# SCH_MinijetengineECU_20260709.net
KiCad netlist of a schematic drawn in EasyEDA
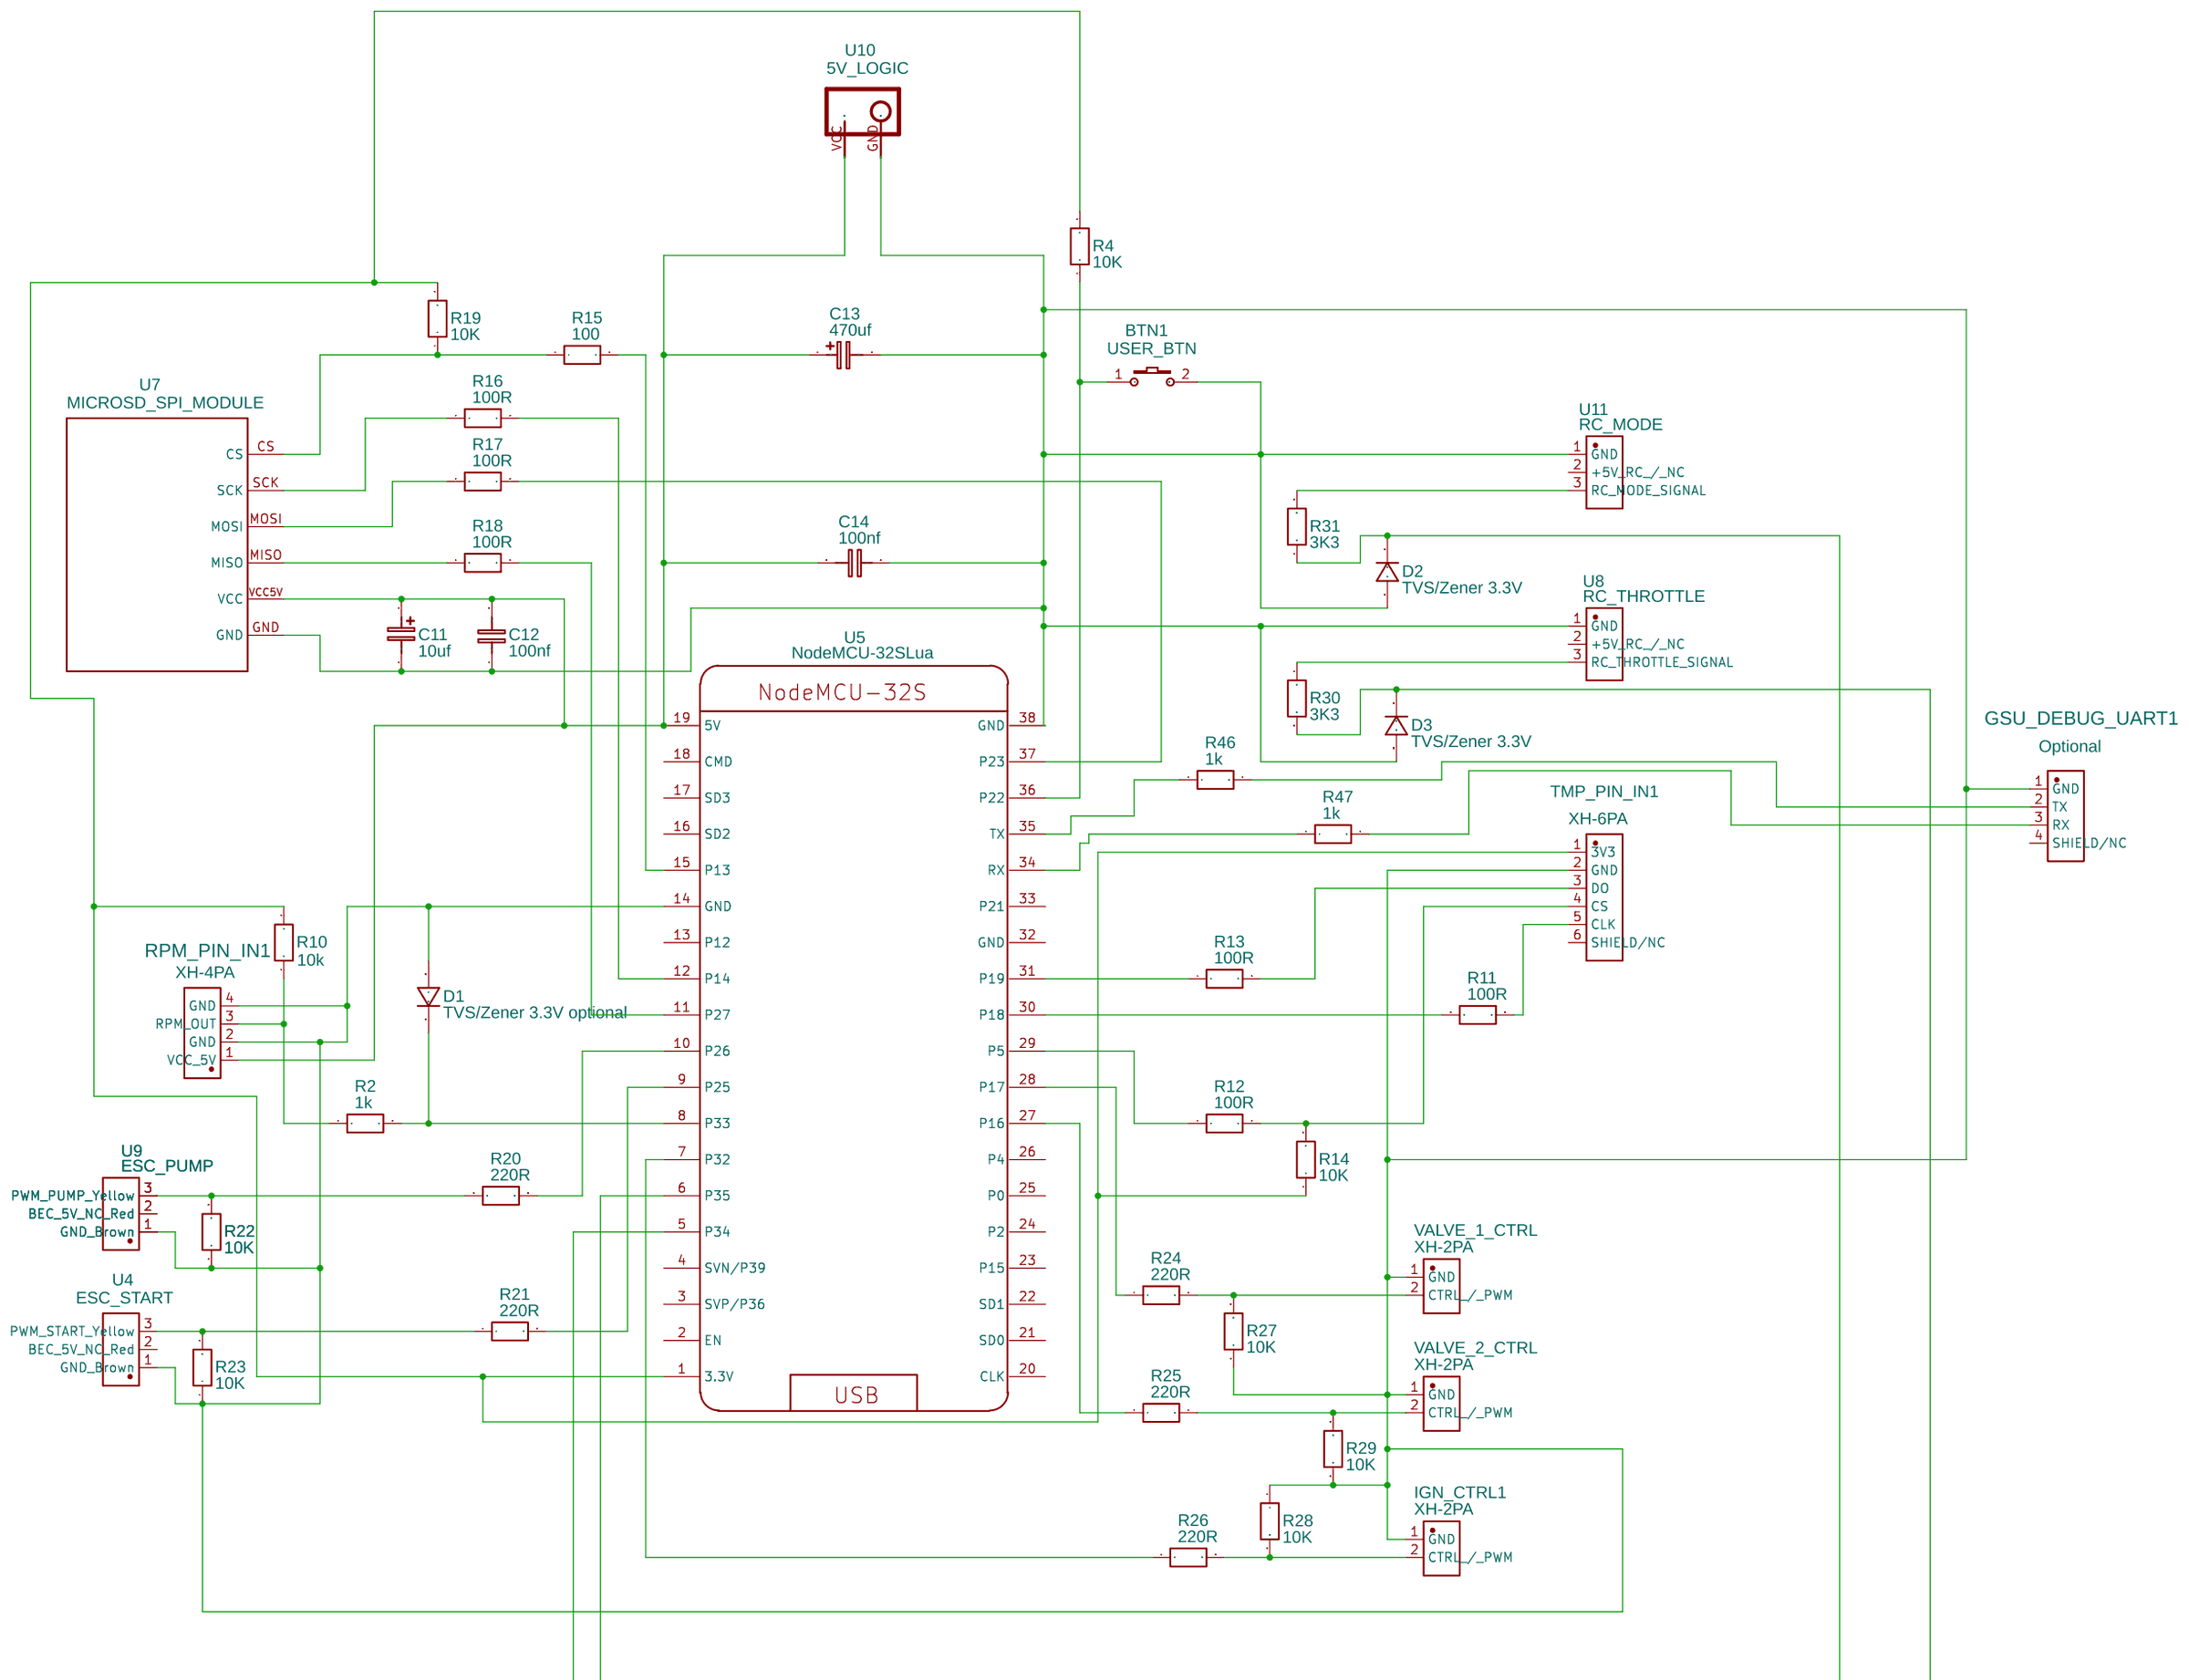
[diagram p0: ECU_JET]
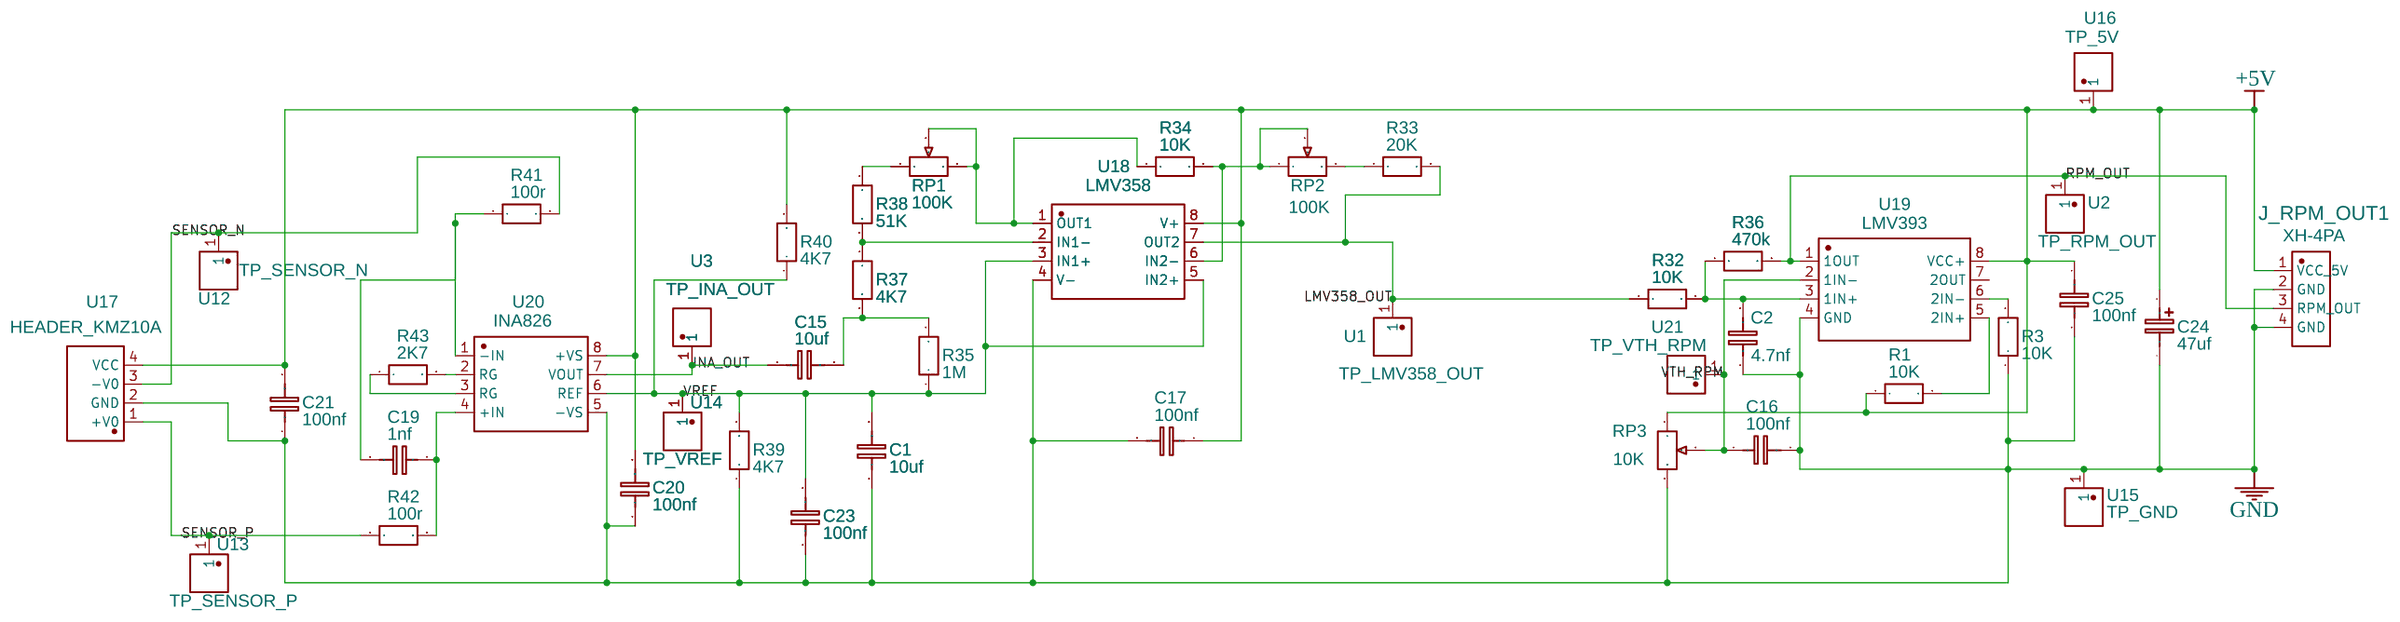
[diagram p1: RPM_Sensor]
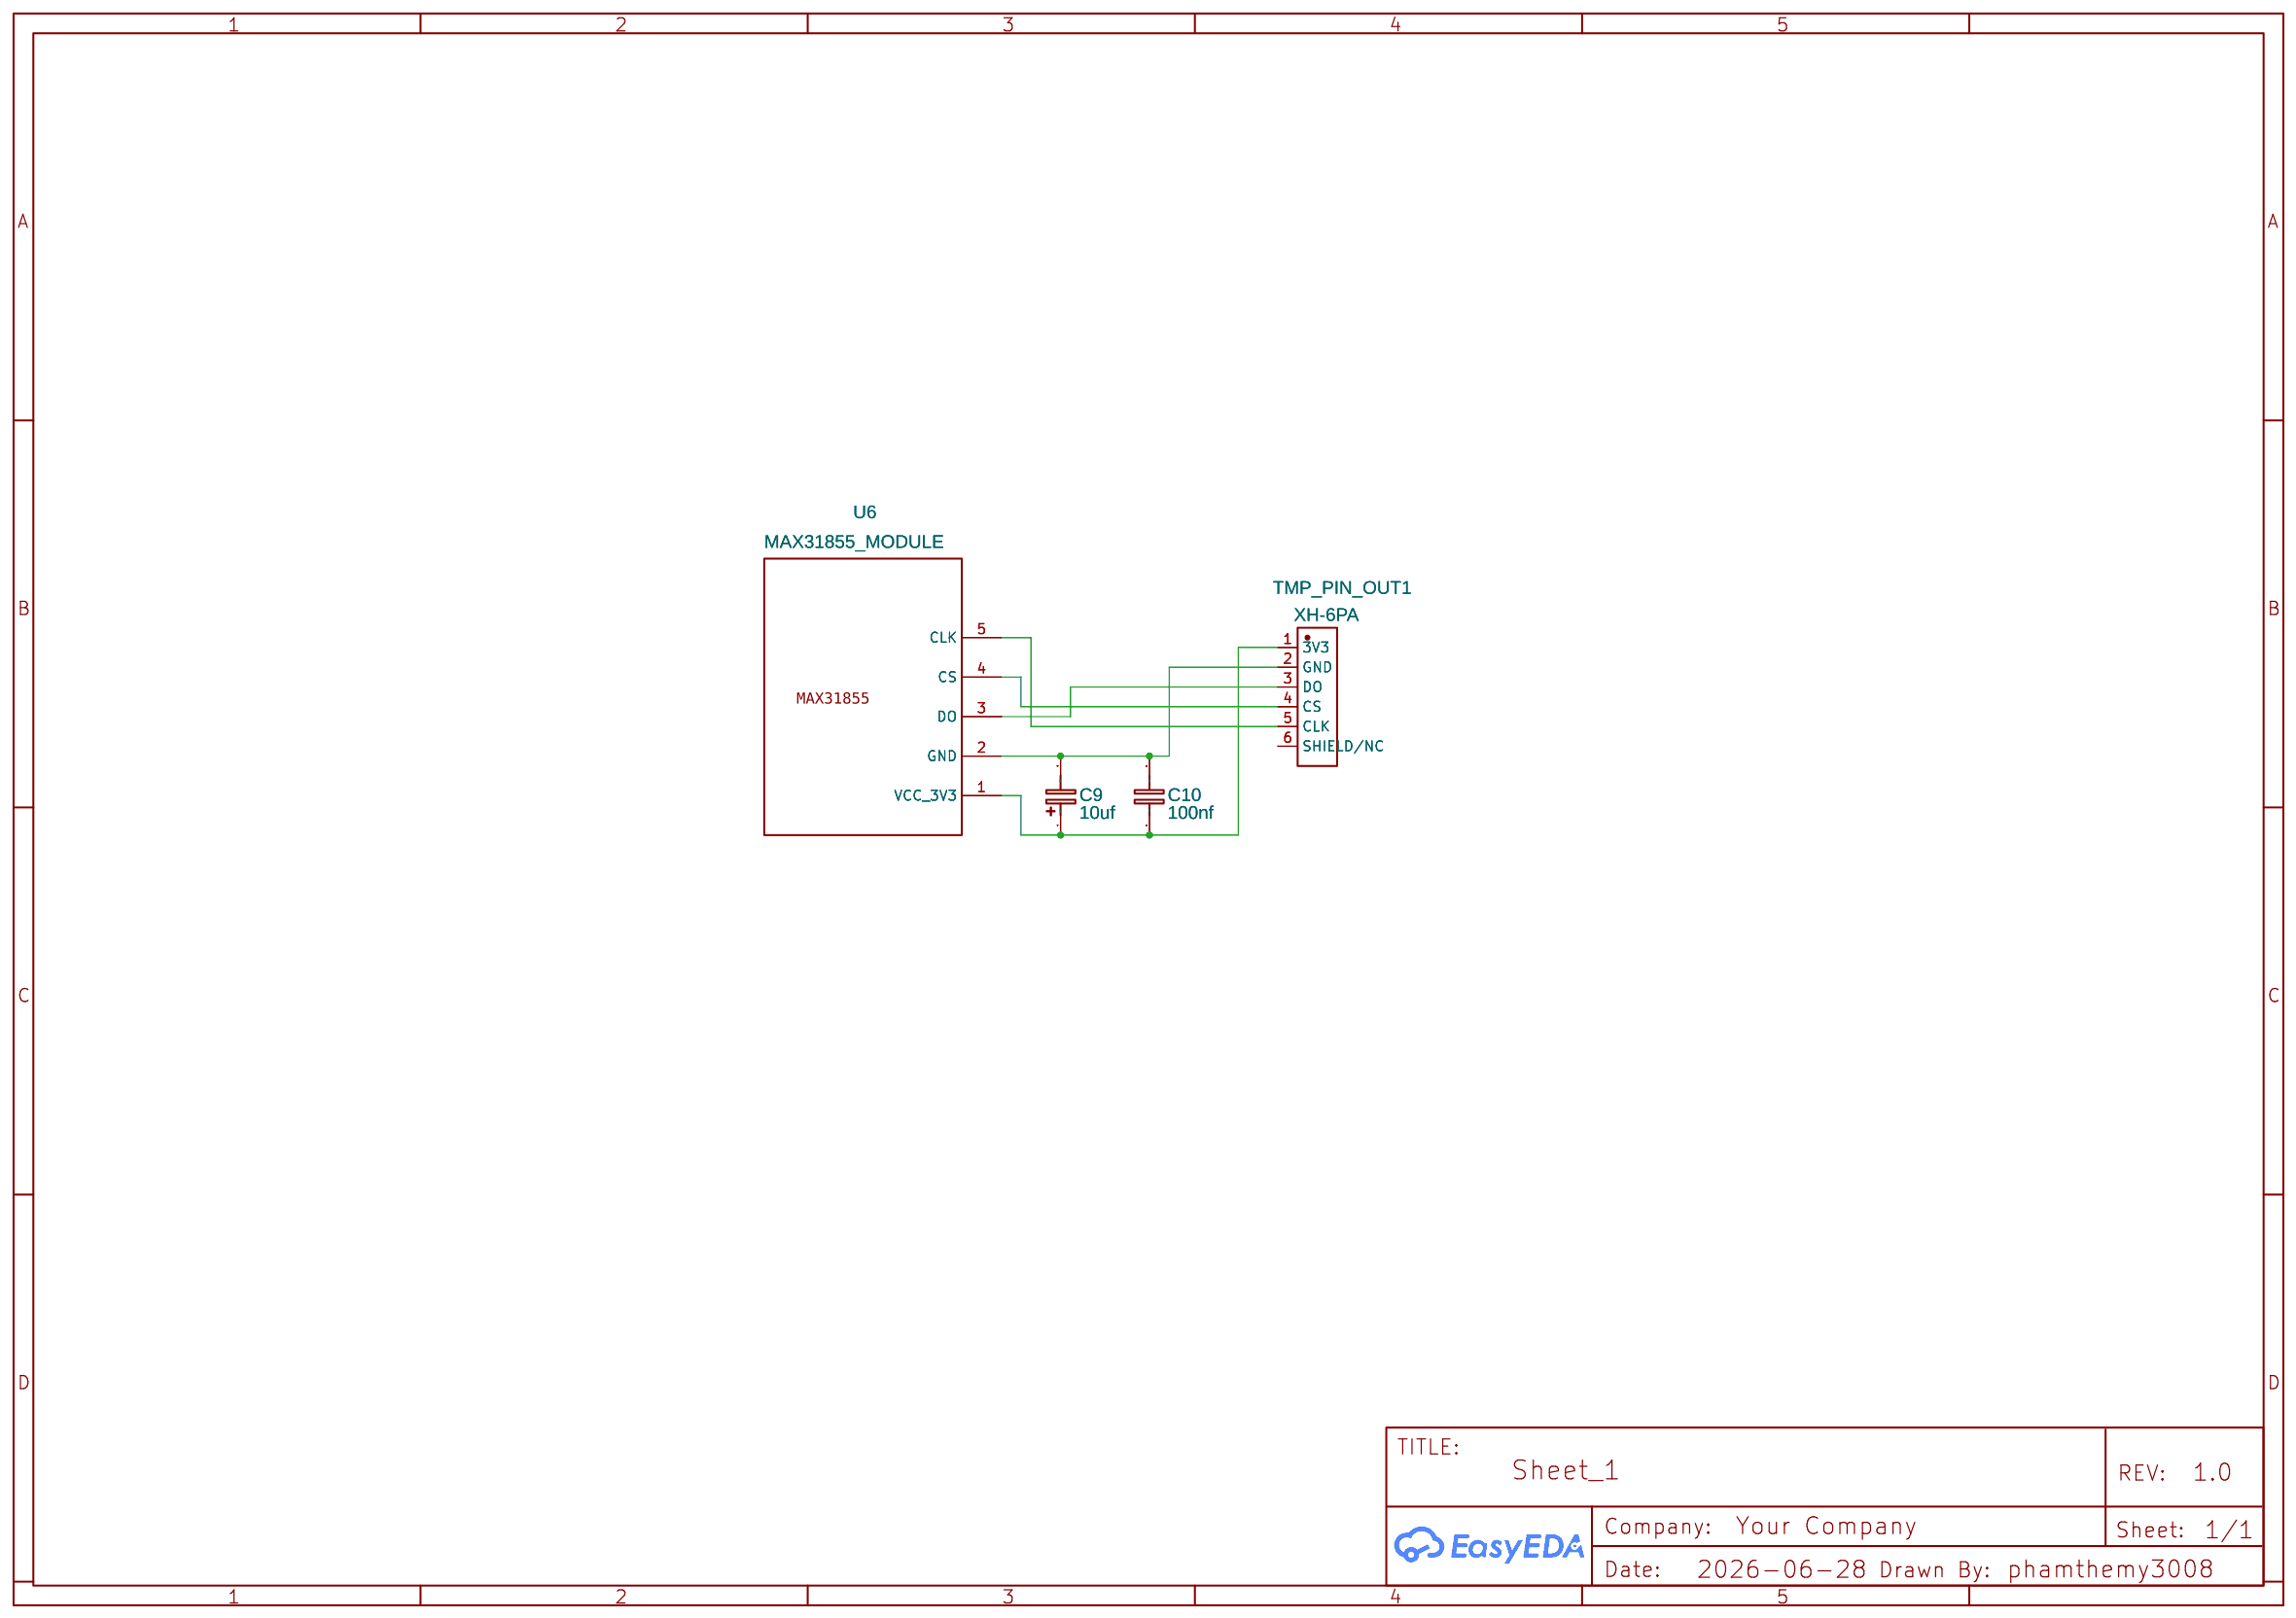
[diagram p2: Temperature_Sensor]

(export (version "E")
  (design (tool "Eeschema 10.0.6"))
  (components
    (comp (ref "BTN1")
      (value "USER_BTN")
      (fields (field (name "Manufacturer Part") "K2-1107ST-A4SW-06"))
      (libsource (lib "") (part "K2-3.6×6.1_SMD"))
    )
    (comp (ref "C11") (value "10uf") (libsource (lib "") (part "C_Tan_SMD_A_EU")))
    (comp (ref "C12") (value "100nf") (libsource (lib "") (part "C_0603_EU_1")))
    (comp (ref "C13") (value "470uf") (libsource (lib "") (part "C_Tan_SMD_A_EU_1")))
    (comp (ref "C14") (value "100nf") (libsource (lib "") (part "C_0603_EU")))
    (comp (ref "D1") (value "TVS/Zener 3.3V optional") (libsource (lib "") (part "1N4007W_1")))
    (comp (ref "D2") (value "TVS/Zener 3.3V") (libsource (lib "") (part "1N4007W")))
    (comp (ref "D3") (value "TVS/Zener 3.3V") (libsource (lib "") (part "1N4007W")))
    (comp (ref "GSU_DEBUG_UART1")
      (value "Optional")
      (fields (field (name "Manufacturer Part") "XH-4PA") (field (name "Manufacturer") "ZHOURI(洲日)"))
      (libsource (lib "") (part "XH-4PA_1"))
    )
    (comp (ref "IGN_CTRL1")
      (value "XH-2PA")
      (fields (field (name "Manufacturer") "ZHOURI(洲日)"))
      (libsource (lib "") (part "XH-2PA_2"))
    )
    (comp (ref "R2") (value "1k") (libsource (lib "") (part "R_0603_EU")))
    (comp (ref "R4") (value "10K") (libsource (lib "") (part "R_0603_EU_1")))
    (comp (ref "R10") (value "10k") (libsource (lib "") (part "R_0603_EU_1")))
    (comp (ref "R11") (value "100R") (libsource (lib "") (part "R_0603_EU")))
    (comp (ref "R12") (value "100R") (libsource (lib "") (part "R_0603_EU")))
    (comp (ref "R13") (value "100R") (libsource (lib "") (part "R_0603_EU")))
    (comp (ref "R14") (value "10K") (libsource (lib "") (part "R_0603_EU_1")))
    (comp (ref "R15") (value "100") (libsource (lib "") (part "R_0603_EU")))
    (comp (ref "R16") (value "100R") (libsource (lib "") (part "R_0603_EU")))
    (comp (ref "R17") (value "100R") (libsource (lib "") (part "R_0603_EU")))
    (comp (ref "R18") (value "100R") (libsource (lib "") (part "R_0603_EU")))
    (comp (ref "R19") (value "10K") (libsource (lib "") (part "R_0603_EU_1")))
    (comp (ref "R20") (value "220R") (libsource (lib "") (part "R_0603_EU")))
    (comp (ref "R21") (value "220R") (libsource (lib "") (part "R_0603_EU")))
    (comp (ref "R22") (value "10K") (libsource (lib "") (part "R_0603_EU_1")))
    (comp (ref "R23") (value "10K") (libsource (lib "") (part "R_0603_EU_1")))
    (comp (ref "R24") (value "220R") (libsource (lib "") (part "R_0603_EU")))
    (comp (ref "R25") (value "220R") (libsource (lib "") (part "R_0603_EU")))
    (comp (ref "R26") (value "220R") (libsource (lib "") (part "R_0603_EU")))
    (comp (ref "R27") (value "10K") (libsource (lib "") (part "R_0603_EU_1")))
    (comp (ref "R28") (value "10K") (libsource (lib "") (part "R_0603_EU_2")))
    (comp (ref "R29") (value "10K") (libsource (lib "") (part "R_0603_EU_1")))
    (comp (ref "R30") (value "3K3") (libsource (lib "") (part "R_0603_EU_2")))
    (comp (ref "R31") (value "3K3") (libsource (lib "") (part "R_0603_EU_1")))
    (comp (ref "R46") (value "1k") (libsource (lib "") (part "R_0603_EU")))
    (comp (ref "R47") (value "1k") (libsource (lib "") (part "R_0603_EU")))
    (comp (ref "RPM_PIN_IN1")
      (value "XH-4PA")
      (fields (field (name "Manufacturer") "ZHOURI(洲日)"))
      (libsource (lib "") (part "XH-4PA"))
    )
    (comp (ref "TMP_PIN_IN1")
      (value "XH-6PA")
      (fields (field (name "Manufacturer") "ZHOURI(洲日)"))
      (libsource (lib "") (part "XH-6PA"))
    )
    (comp (ref "U4")
      (value "ESC_START")
      (fields (field (name "Manufacturer Part") "Header35.08-3P"))
      (libsource (lib "") (part "HEADER35.08-3P"))
    )
    (comp (ref "U5")
      (value "NodeMCU-32SLua")
      (fields (field (name "Manufacturer") "Ai-Thinker"))
      (libsource (lib "") (part "NodeMCU-32SLua"))
    )
    (comp (ref "U7") (value "MICROSD_SPI_MODULE") (libsource (lib "") (part "MICROSD_SPI_MODULE")))
    (comp (ref "U8")
      (value "RC_THROTTLE")
      (fields (field (name "Manufacturer Part") "Header35.08-3P"))
      (libsource (lib "") (part "HEADER35.08-3P_1"))
    )
    (comp (ref "U9")
      (value "ESC_PUMP")
      (fields (field (name "Manufacturer Part") "Header35.08-3P"))
      (libsource (lib "") (part "HEADER35.08-3P_3"))
    )
    (comp (ref "U10") (value "5V_LOGIC") (libsource (lib "") (part "DOMINO-2P-5.08")))
    (comp (ref "U11")
      (value "RC_MODE")
      (fields (field (name "Manufacturer Part") "Header35.08-3P"))
      (libsource (lib "") (part "HEADER35.08-3P_2"))
    )
    (comp (ref "VALVE_1_CTRL")
      (value "XH-2PA")
      (fields (field (name "Manufacturer") "ZHOURI(洲日)"))
      (libsource (lib "") (part "XH-2PA"))
    )
    (comp (ref "VALVE_2_CTRL")
      (value "XH-2PA")
      (fields (field (name "Manufacturer") "ZHOURI(洲日)"))
      (libsource (lib "") (part "XH-2PA_1"))
    )
    (comp (ref "C1") (value "10uf") (libsource (lib "") (part "C_0603_EU")))
    (comp (ref "C2") (value "4.7nf") (libsource (lib "") (part "C_0603_EU_1")))
    (comp (ref "C15") (value "10uf") (libsource (lib "") (part "C_0603_EU_4")))
    (comp (ref "C16") (value "100nf") (libsource (lib "") (part "C_0603_EU_3")))
    (comp (ref "C17") (value "100nf") (libsource (lib "") (part "C_0603_EU_5")))
    (comp (ref "C19") (value "1nf") (libsource (lib "") (part "C_0603_EU_2")))
    (comp (ref "C20") (value "100nf") (libsource (lib "") (part "C_0603_EU")))
    (comp (ref "C21") (value "100nf") (libsource (lib "") (part "C_0603_EU")))
    (comp (ref "C23") (value "100nf") (libsource (lib "") (part "C_0603_EU")))
    (comp (ref "C24")
      (value "47uf")
      (fields (field (name "Manufacturer Part") "TAJB476K010RNJ") (field (name "Manufacturer") "Kyocera AVX"))
      (libsource (lib "") (part "C_Tan_SMD_A_EU"))
    )
    (comp (ref "C25") (value "100nf") (libsource (lib "") (part "C_0603_EU_6")))
    (comp (ref "J_RPM_OUT1")
      (value "XH-4PA")
      (fields (field (name "Manufacturer") "ZHOURI(洲日)"))
      (libsource (lib "") (part "XH-4PA"))
    )
    (comp (ref "R1") (value "10K") (libsource (lib "") (part "R_0603_EU")))
    (comp (ref "R3") (value "10K") (libsource (lib "") (part "R_0603_EU_2")))
    (comp (ref "R32") (value "10K") (libsource (lib "") (part "R_0603_EU")))
    (comp (ref "R33") (value "20K") (libsource (lib "") (part "R_0603_EU")))
    (comp (ref "R34") (value "10K") (libsource (lib "") (part "R_0603_EU")))
    (comp (ref "R35") (value "1M") (libsource (lib "") (part "R_0603_EU_2")))
    (comp (ref "R36") (value "470k") (libsource (lib "") (part "R_0603_EU")))
    (comp (ref "R37") (value "4K7") (libsource (lib "") (part "R_0603_EU_1")))
    (comp (ref "R38") (value "51K") (libsource (lib "") (part "R_0603_EU_1")))
    (comp (ref "R39") (value "4K7") (libsource (lib "") (part "R_0603_EU_2")))
    (comp (ref "R40") (value "4K7") (libsource (lib "") (part "R_0603_EU_2")))
    (comp (ref "R41") (value "100r") (libsource (lib "") (part "R_0603_EU")))
    (comp (ref "R42") (value "100r") (libsource (lib "") (part "R_0603_EU")))
    (comp (ref "R43") (value "2K7") (libsource (lib "") (part "R_0603_EU")))
    (comp (ref "RP1") (value "100K") (libsource (lib "") (part "R_3386P_EU")))
    (comp (ref "RP2") (value "100K") (libsource (lib "") (part "R_3386P_EU")))
    (comp (ref "RP3") (value "10K") (libsource (lib "") (part "R_3386P_EU_1")))
    (comp (ref "U1")
      (value "TP_LMV358_OUT")
      (fields
        (field (name "Manufacturer Part") "YZP0352-20095-01")
        (field (name "Manufacturer") "Xinyangze(鑫扬泽)")
      )
      (libsource (lib "") (part "YZP0352-20095-01_1"))
    )
    (comp (ref "U2")
      (value "TP_RPM_OUT")
      (fields
        (field (name "Manufacturer Part") "YZP0352-20095-01")
        (field (name "Manufacturer") "Xinyangze(鑫扬泽)")
      )
      (libsource (lib "") (part "YZP0352-20095-01_1"))
    )
    (comp (ref "U3")
      (value "TP_INA_OUT")
      (fields
        (field (name "Manufacturer Part") "YZP0352-20095-01")
        (field (name "Manufacturer") "Xinyangze(鑫扬泽)")
      )
      (libsource (lib "") (part "YZP0352-20095-01"))
    )
    (comp (ref "U12")
      (value "TP_SENSOR_N")
      (fields
        (field (name "Manufacturer Part") "YZP0352-20095-01")
        (field (name "Manufacturer") "Xinyangze(鑫扬泽)")
      )
      (libsource (lib "") (part "YZP0352-20095-01_1"))
    )
    (comp (ref "U13")
      (value "TP_SENSOR_P")
      (fields
        (field (name "Manufacturer Part") "YZP0352-20095-01")
        (field (name "Manufacturer") "Xinyangze(鑫扬泽)")
      )
      (libsource (lib "") (part "YZP0352-20095-01_1"))
    )
    (comp (ref "U14")
      (value "TP_VREF")
      (fields
        (field (name "Manufacturer Part") "YZP0352-20095-01")
        (field (name "Manufacturer") "Xinyangze(鑫扬泽)")
      )
      (libsource (lib "") (part "YZP0352-20095-01_1"))
    )
    (comp (ref "U15")
      (value "TP_GND")
      (fields
        (field (name "Manufacturer Part") "YZP0352-20095-01")
        (field (name "Manufacturer") "Xinyangze(鑫扬泽)")
      )
      (libsource (lib "") (part "YZP0352-20095-01_1"))
    )
    (comp (ref "U16")
      (value "TP_5V")
      (fields
        (field (name "Manufacturer Part") "YZP0352-20095-01")
        (field (name "Manufacturer") "Xinyangze(鑫扬泽)")
      )
      (libsource (lib "") (part "YZP0352-20095-01"))
    )
    (comp (ref "U17") (value "HEADER_KMZ10A") (libsource (lib "") (part "Magnetic Sensor")))
    (comp (ref "U18")
      (value "LMV358")
      (fields (field (name "Manufacturer") "TECH PUBLIC"))
      (libsource (lib "") (part "LM358DGKRG"))
    )
    (comp (ref "U19")
      (value "LMV393")
      (fields (field (name "Manufacturer Part") "LMV393IDR") (field (name "Manufacturer") "TI(德州仪器)"))
      (libsource (lib "") (part "LMV393IDR"))
    )
    (comp (ref "U20")
      (value "INA826")
      (fields (field (name "Manufacturer Part") "INA826AID") (field (name "Manufacturer") "TI(德州仪器)"))
      (libsource (lib "") (part "INA826AID"))
    )
    (comp (ref "U21")
      (value "TP_VTH_RPM")
      (fields
        (field (name "Manufacturer Part") "YZP0352-20095-01")
        (field (name "Manufacturer") "Xinyangze(鑫扬泽)")
      )
      (libsource (lib "") (part "YZP0352-20095-01_2"))
    )
    (comp (ref "C9") (value "10uf") (libsource (lib "") (part "C_Tan_SMD_A_EU")))
    (comp (ref "C10") (value "100nf") (libsource (lib "") (part "C_0603_EU")))
    (comp (ref "TMP_PIN_OUT1")
      (value "XH-6PA")
      (fields (field (name "Manufacturer") "ZHOURI(洲日)"))
      (libsource (lib "") (part "XH-6PA"))
    )
    (comp (ref "U6") (value "MAX31855_MODULE") (libsource (lib "") (part "MAX31855_MODULE")))
  )
  (nets
    (net (code "1") (name "+5V") (class "Default")
      (node (ref "C17") (pin "1") (pinfunction "1_1") (pintype "unspecified"))
      (node (ref "C20") (pin "2") (pinfunction "2_2") (pintype "unspecified"))
      (node (ref "C21") (pin "2") (pinfunction "2_2") (pintype "unspecified"))
      (node (ref "C24") (pin "+") (pinfunction "1_+") (pintype "unspecified"))
      (node (ref "C25") (pin "1") (pinfunction "2_1") (pintype "unspecified"))
      (node (ref "J_RPM_OUT1") (pin "1") (pinfunction "VCC_5V_1") (pintype "unspecified"))
      (node (ref "R1") (pin "1") (pinfunction "1_1") (pintype "unspecified"))
      (node (ref "R40") (pin "2") (pinfunction "2_2") (pintype "unspecified"))
      (node (ref "RP3") (pin "1") (pinfunction "1_1") (pintype "input"))
      (node (ref "U16") (pin "1") (pinfunction "1_1") (pintype "unspecified"))
      (node (ref "U17") (pin "4") (pinfunction "VCC_4") (pintype "unspecified"))
      (node (ref "U18") (pin "8") (pinfunction "V+_8") (pintype "unspecified"))
      (node (ref "U19") (pin "8") (pinfunction "VCC+_8") (pintype "unspecified"))
      (node (ref "U20") (pin "8") (pinfunction "+VS_8") (pintype "unspecified"))
    )
    (net (code "2") (name "GND") (class "Default")
      (node (ref "C1") (pin "1") (pinfunction "1_1") (pintype "unspecified"))
      (node (ref "C16") (pin "2") (pinfunction "2_2") (pintype "unspecified"))
      (node (ref "C17") (pin "2") (pinfunction "2_2") (pintype "unspecified"))
      (node (ref "C2") (pin "1") (pinfunction "1_1") (pintype "unspecified"))
      (node (ref "C20") (pin "1") (pinfunction "1_1") (pintype "unspecified"))
      (node (ref "C21") (pin "1") (pinfunction "1_1") (pintype "unspecified"))
      (node (ref "C23") (pin "1") (pinfunction "1_1") (pintype "unspecified"))
      (node (ref "C24") (pin "-") (pinfunction "2_-") (pintype "unspecified"))
      (node (ref "C25") (pin "2") (pinfunction "1_2") (pintype "unspecified"))
      (node (ref "J_RPM_OUT1") (pin "2") (pinfunction "GND_2") (pintype "unspecified"))
      (node (ref "J_RPM_OUT1") (pin "4") (pinfunction "GND_4") (pintype "unspecified"))
      (node (ref "R3") (pin "1") (pinfunction "1_1") (pintype "unspecified"))
      (node (ref "R39") (pin "1") (pinfunction "1_1") (pintype "unspecified"))
      (node (ref "RP3") (pin "3") (pinfunction "3_3") (pintype "input"))
      (node (ref "U15") (pin "1") (pinfunction "1_1") (pintype "unspecified"))
      (node (ref "U17") (pin "2") (pinfunction "GND_2") (pintype "unspecified"))
      (node (ref "U18") (pin "4") (pinfunction "V-_4") (pintype "unspecified"))
      (node (ref "U19") (pin "4") (pinfunction "GND_4") (pintype "unspecified"))
      (node (ref "U20") (pin "5") (pinfunction "-VS_5") (pintype "unspecified"))
    )
    (net (code "3") (name "INA_OUT") (class "Default")
      (node (ref "C15") (pin "1") (pinfunction "1_1") (pintype "unspecified"))
      (node (ref "U20") (pin "7") (pinfunction "VOUT_7") (pintype "unspecified"))
      (node (ref "U3") (pin "1") (pinfunction "1_1") (pintype "unspecified"))
    )
    (net (code "4") (name "LMV358_OUT") (class "Default")
      (node (ref "R32") (pin "1") (pinfunction "1_1") (pintype "unspecified"))
      (node (ref "R33") (pin "2") (pinfunction "2_2") (pintype "unspecified"))
      (node (ref "U1") (pin "1") (pinfunction "1_1") (pintype "unspecified"))
      (node (ref "U18") (pin "7") (pinfunction "OUT2_7") (pintype "unspecified"))
    )
    (net (code "5") (name "Net-(C15-Pad2)") (class "Default")
      (node (ref "C15") (pin "2") (pinfunction "2_2") (pintype "unspecified"))
      (node (ref "R35") (pin "2") (pinfunction "2_2") (pintype "unspecified"))
      (node (ref "R37") (pin "2") (pinfunction "2_2") (pintype "unspecified"))
    )
    (net (code "6") (name "Net-(D1-1)") (class "Default")
      (node (ref "D1") (pin "P$1") (pinfunction "1_P$1") (pintype "unspecified"))
      (node (ref "R2") (pin "2") (pinfunction "2_2") (pintype "unspecified"))
      (node (ref "U5") (pin "8") (pinfunction "P33_8") (pintype "unspecified"))
    )
    (net (code "7") (name "Net-(D1-2)") (class "Default")
      (node (ref "BTN1") (pin "2") (pinfunction "2_2") (pintype "unspecified"))
      (node (ref "C11") (pin "2") (pinfunction "2_2") (pintype "unspecified"))
      (node (ref "C12") (pin "1") (pinfunction "1_1") (pintype "unspecified"))
      (node (ref "C13") (pin "2") (pinfunction "2_2") (pintype "unspecified"))
      (node (ref "C14") (pin "1") (pinfunction "1_1") (pintype "unspecified"))
      (node (ref "D1") (pin "P$2") (pinfunction "2_P$2") (pintype "unspecified"))
      (node (ref "D2") (pin "P$2") (pinfunction "2_P$2") (pintype "unspecified"))
      (node (ref "D3") (pin "P$2") (pinfunction "2_P$2") (pintype "unspecified"))
      (node (ref "GSU_DEBUG_UART1") (pin "1") (pinfunction "GND_1") (pintype "unspecified"))
      (node (ref "IGN_CTRL1") (pin "1") (pinfunction "GND_1") (pintype "unspecified"))
      (node (ref "R22") (pin "1") (pinfunction "1_1") (pintype "unspecified"))
      (node (ref "R23") (pin "1") (pinfunction "1_1") (pintype "unspecified"))
      (node (ref "R27") (pin "1") (pinfunction "1_1") (pintype "unspecified"))
      (node (ref "R28") (pin "1") (pinfunction "1_1") (pintype "unspecified"))
      (node (ref "R29") (pin "1") (pinfunction "1_1") (pintype "unspecified"))
      (node (ref "RPM_PIN_IN1") (pin "2") (pinfunction "GND_2") (pintype "unspecified"))
      (node (ref "RPM_PIN_IN1") (pin "4") (pinfunction "GND_4") (pintype "unspecified"))
      (node (ref "TMP_PIN_IN1") (pin "2") (pinfunction "GND_2") (pintype "unspecified"))
      (node (ref "U10") (pin "GND") (pinfunction "GND_GND") (pintype "passive"))
      (node (ref "U11") (pin "1") (pinfunction "GND_1") (pintype "unspecified"))
      (node (ref "U4") (pin "1") (pinfunction "GND_Brown_1") (pintype "unspecified"))
      (node (ref "U5") (pin "14") (pinfunction "GND_14") (pintype "unspecified"))
      (node (ref "U5") (pin "38") (pinfunction "GND_38") (pintype "unspecified"))
      (node (ref "U7") (pin "GND") (pinfunction "GND_GND") (pintype "input"))
      (node (ref "U8") (pin "1") (pinfunction "GND_1") (pintype "unspecified"))
      (node (ref "U9") (pin "1") (pinfunction "GND_Brown_1") (pintype "unspecified"))
      (node (ref "VALVE_1_CTRL") (pin "1") (pinfunction "GND_1") (pintype "unspecified"))
      (node (ref "VALVE_2_CTRL") (pin "1") (pinfunction "GND_1") (pintype "unspecified"))
    )
    (net (code "8") (name "Net-(D2-1)") (class "Default")
      (node (ref "D2") (pin "P$1") (pinfunction "1_P$1") (pintype "unspecified"))
      (node (ref "R31") (pin "1") (pinfunction "1_1") (pintype "unspecified"))
      (node (ref "U5") (pin "6") (pinfunction "P35_6") (pintype "unspecified"))
    )
    (net (code "9") (name "Net-(D3-1)") (class "Default")
      (node (ref "D3") (pin "P$1") (pinfunction "1_P$1") (pintype "unspecified"))
      (node (ref "R30") (pin "2") (pinfunction "2_2") (pintype "unspecified"))
      (node (ref "U5") (pin "5") (pinfunction "P34_5") (pintype "unspecified"))
    )
    (net (code "10") (name "Net-(GSU_DEBUG_UART1-RX)") (class "Default")
      (node (ref "GSU_DEBUG_UART1") (pin "3") (pinfunction "RX_3") (pintype "unspecified"))
      (node (ref "R47") (pin "2") (pinfunction "2_2") (pintype "unspecified"))
    )
    (net (code "11") (name "Net-(GSU_DEBUG_UART1-TX)") (class "Default")
      (node (ref "GSU_DEBUG_UART1") (pin "2") (pinfunction "TX_2") (pintype "unspecified"))
      (node (ref "R46") (pin "2") (pinfunction "2_2") (pintype "unspecified"))
    )
    (net (code "12") (name "Net-(IGN_CTRL1-CTRL_{slash}_PWM)") (class "Default")
      (node (ref "IGN_CTRL1") (pin "2") (pinfunction "CTRL_/_PWM_2") (pintype "unspecified"))
      (node (ref "R26") (pin "2") (pinfunction "2_2") (pintype "unspecified"))
      (node (ref "R28") (pin "2") (pinfunction "2_2") (pintype "unspecified"))
    )
    (net (code "13") (name "Net-(R15-Pad1)") (class "Default")
      (node (ref "R15") (pin "1") (pinfunction "1_1") (pintype "unspecified"))
      (node (ref "R19") (pin "1") (pinfunction "1_1") (pintype "unspecified"))
      (node (ref "U7") (pin "CS") (pinfunction "CS_CS") (pintype "bidirectional"))
    )
    (net (code "14") (name "Net-(R16-Pad1)") (class "Default")
      (node (ref "R16") (pin "1") (pinfunction "1_1") (pintype "unspecified"))
      (node (ref "U7") (pin "SCK") (pinfunction "SCK_SCK") (pintype "bidirectional"))
    )
    (net (code "15") (name "Net-(R17-Pad1)") (class "Default")
      (node (ref "R17") (pin "1") (pinfunction "1_1") (pintype "unspecified"))
      (node (ref "U7") (pin "MOSI") (pinfunction "MOSI_MOSI") (pintype "input"))
    )
    (net (code "16") (name "Net-(R18-Pad1)") (class "Default")
      (node (ref "R18") (pin "1") (pinfunction "1_1") (pintype "unspecified"))
      (node (ref "U7") (pin "MISO") (pinfunction "MISO_MISO") (pintype "output"))
    )
    (net (code "17") (name "Net-(R33-Pad1)") (class "Default")
      (node (ref "R33") (pin "1") (pinfunction "1_1") (pintype "unspecified"))
      (node (ref "RP2") (pin "3") (pinfunction "3_3") (pintype "input"))
    )
    (net (code "18") (name "Net-(R38-Pad1)") (class "Default")
      (node (ref "R38") (pin "1") (pinfunction "1_1") (pintype "unspecified"))
      (node (ref "RP1") (pin "1") (pinfunction "1_1") (pintype "input"))
    )
    (net (code "19") (name "Net-(R43-Pad1)") (class "Default")
      (node (ref "R43") (pin "1") (pinfunction "1_1") (pintype "unspecified"))
      (node (ref "U20") (pin "3") (pinfunction "RG_3") (pintype "unspecified"))
    )
    (net (code "20") (name "Net-(R43-Pad2)") (class "Default")
      (node (ref "R43") (pin "2") (pinfunction "2_2") (pintype "unspecified"))
      (node (ref "U20") (pin "2") (pinfunction "RG_2") (pintype "unspecified"))
    )
    (net (code "21") (name "Net-(RPM_PIN_IN1-RPM_OUT)") (class "Default")
      (node (ref "R10") (pin "1") (pinfunction "1_1") (pintype "unspecified"))
      (node (ref "R2") (pin "1") (pinfunction "1_1") (pintype "unspecified"))
      (node (ref "RPM_PIN_IN1") (pin "3") (pinfunction "RPM_OUT_3") (pintype "unspecified"))
    )
    (net (code "22") (name "Net-(RPM_PIN_IN1-VCC_5V)") (class "Default")
      (node (ref "C11") (pin "1") (pinfunction "1_1") (pintype "unspecified"))
      (node (ref "C12") (pin "2") (pinfunction "2_2") (pintype "unspecified"))
      (node (ref "C13") (pin "1") (pinfunction "1_1") (pintype "unspecified"))
      (node (ref "C14") (pin "2") (pinfunction "2_2") (pintype "unspecified"))
      (node (ref "RPM_PIN_IN1") (pin "1") (pinfunction "VCC_5V_1") (pintype "unspecified"))
      (node (ref "U10") (pin "VCC") (pinfunction "VCC_VCC") (pintype "passive"))
      (node (ref "U5") (pin "19") (pinfunction "5V_19") (pintype "unspecified"))
      (node (ref "U7") (pin "VCC5V") (pinfunction "VCC_VCC5V") (pintype "input"))
    )
    (net (code "23") (name "Net-(TMP_PIN_IN1-3V3)") (class "Default")
      (node (ref "R10") (pin "2") (pinfunction "2_2") (pintype "unspecified"))
      (node (ref "R14") (pin "1") (pinfunction "1_1") (pintype "unspecified"))
      (node (ref "R19") (pin "2") (pinfunction "2_2") (pintype "unspecified"))
      (node (ref "R4") (pin "2") (pinfunction "2_2") (pintype "unspecified"))
      (node (ref "TMP_PIN_IN1") (pin "1") (pinfunction "3V3_1") (pintype "unspecified"))
      (node (ref "U5") (pin "1") (pinfunction "3.3V_1") (pintype "unspecified"))
    )
    (net (code "24") (name "Net-(TMP_PIN_IN1-CLK)") (class "Default")
      (node (ref "R11") (pin "2") (pinfunction "2_2") (pintype "unspecified"))
      (node (ref "TMP_PIN_IN1") (pin "5") (pinfunction "CLK_5") (pintype "unspecified"))
    )
    (net (code "25") (name "Net-(TMP_PIN_IN1-CS)") (class "Default")
      (node (ref "R12") (pin "2") (pinfunction "2_2") (pintype "unspecified"))
      (node (ref "R14") (pin "2") (pinfunction "2_2") (pintype "unspecified"))
      (node (ref "TMP_PIN_IN1") (pin "4") (pinfunction "CS_4") (pintype "unspecified"))
    )
    (net (code "26") (name "Net-(TMP_PIN_IN1-DO)") (class "Default")
      (node (ref "R13") (pin "2") (pinfunction "2_2") (pintype "unspecified"))
      (node (ref "TMP_PIN_IN1") (pin "3") (pinfunction "DO_3") (pintype "unspecified"))
    )
    (net (code "27") (name "Net-(TMP_PIN_OUT1-3V3)") (class "Default")
      (node (ref "C10") (pin "1") (pinfunction "1_1") (pintype "unspecified"))
      (node (ref "C9") (pin "1") (pinfunction "1_1") (pintype "unspecified"))
      (node (ref "TMP_PIN_OUT1") (pin "1") (pinfunction "3V3_1") (pintype "passive"))
      (node (ref "U6") (pin "1") (pinfunction "VCC_3V3_1") (pintype "bidirectional"))
    )
    (net (code "28") (name "Net-(TMP_PIN_OUT1-CLK)") (class "Default")
      (node (ref "TMP_PIN_OUT1") (pin "5") (pinfunction "CLK_5") (pintype "unspecified"))
      (node (ref "U6") (pin "5") (pinfunction "CLK_5") (pintype "output"))
    )
    (net (code "29") (name "Net-(TMP_PIN_OUT1-CS)") (class "Default")
      (node (ref "TMP_PIN_OUT1") (pin "4") (pinfunction "CS_4") (pintype "unspecified"))
      (node (ref "U6") (pin "4") (pinfunction "CS_4") (pintype "input"))
    )
    (net (code "30") (name "Net-(TMP_PIN_OUT1-DO)") (class "Default")
      (node (ref "TMP_PIN_OUT1") (pin "3") (pinfunction "DO_3") (pintype "output"))
      (node (ref "U6") (pin "3") (pinfunction "DO_3") (pintype "input"))
    )
    (net (code "31") (name "Net-(TMP_PIN_OUT1-GND)") (class "Default")
      (node (ref "C10") (pin "2") (pinfunction "2_2") (pintype "unspecified"))
      (node (ref "C9") (pin "2") (pinfunction "2_2") (pintype "unspecified"))
      (node (ref "TMP_PIN_OUT1") (pin "2") (pinfunction "GND_2") (pintype "passive"))
      (node (ref "U6") (pin "2") (pinfunction "GND_2") (pintype "bidirectional"))
    )
    (net (code "32") (name "Net-(U4-PWM_START_Yellow)") (class "Default")
      (node (ref "R21") (pin "1") (pinfunction "1_1") (pintype "unspecified"))
      (node (ref "R23") (pin "2") (pinfunction "2_2") (pintype "unspecified"))
      (node (ref "U4") (pin "3") (pinfunction "PWM_START_Yellow_3") (pintype "unspecified"))
    )
    (net (code "33") (name "Net-(U5-P5)") (class "Default")
      (node (ref "R12") (pin "1") (pinfunction "1_1") (pintype "unspecified"))
      (node (ref "U5") (pin "29") (pinfunction "P5_29") (pintype "unspecified"))
    )
    (net (code "34") (name "Net-(U5-P13)") (class "Default")
      (node (ref "R15") (pin "2") (pinfunction "2_2") (pintype "unspecified"))
      (node (ref "U5") (pin "15") (pinfunction "P13_15") (pintype "unspecified"))
    )
    (net (code "35") (name "Net-(U5-P14)") (class "Default")
      (node (ref "R16") (pin "2") (pinfunction "2_2") (pintype "unspecified"))
      (node (ref "U5") (pin "12") (pinfunction "P14_12") (pintype "unspecified"))
    )
    (net (code "36") (name "Net-(U5-P16)") (class "Default")
      (node (ref "R25") (pin "1") (pinfunction "1_1") (pintype "unspecified"))
      (node (ref "U5") (pin "27") (pinfunction "P16_27") (pintype "unspecified"))
    )
    (net (code "37") (name "Net-(U5-P17)") (class "Default")
      (node (ref "R24") (pin "1") (pinfunction "1_1") (pintype "unspecified"))
      (node (ref "U5") (pin "28") (pinfunction "P17_28") (pintype "unspecified"))
    )
    (net (code "38") (name "Net-(U5-P18)") (class "Default")
      (node (ref "R11") (pin "1") (pinfunction "1_1") (pintype "unspecified"))
      (node (ref "U5") (pin "30") (pinfunction "P18_30") (pintype "unspecified"))
    )
    (net (code "39") (name "Net-(U5-P19)") (class "Default")
      (node (ref "R13") (pin "1") (pinfunction "1_1") (pintype "unspecified"))
      (node (ref "U5") (pin "31") (pinfunction "P19_31") (pintype "unspecified"))
    )
    (net (code "40") (name "Net-(U5-P22)") (class "Default")
      (node (ref "BTN1") (pin "1") (pinfunction "1_1") (pintype "unspecified"))
      (node (ref "R4") (pin "1") (pinfunction "1_1") (pintype "unspecified"))
      (node (ref "U5") (pin "36") (pinfunction "P22_36") (pintype "unspecified"))
    )
    (net (code "41") (name "Net-(U5-P23)") (class "Default")
      (node (ref "R17") (pin "2") (pinfunction "2_2") (pintype "unspecified"))
      (node (ref "U5") (pin "37") (pinfunction "P23_37") (pintype "unspecified"))
    )
    (net (code "42") (name "Net-(U5-P25)") (class "Default")
      (node (ref "R21") (pin "2") (pinfunction "2_2") (pintype "unspecified"))
      (node (ref "U5") (pin "9") (pinfunction "P25_9") (pintype "unspecified"))
    )
    (net (code "43") (name "Net-(U5-P26)") (class "Default")
      (node (ref "R20") (pin "2") (pinfunction "2_2") (pintype "unspecified"))
      (node (ref "U5") (pin "10") (pinfunction "P26_10") (pintype "unspecified"))
    )
    (net (code "44") (name "Net-(U5-P27)") (class "Default")
      (node (ref "R18") (pin "2") (pinfunction "2_2") (pintype "unspecified"))
      (node (ref "U5") (pin "11") (pinfunction "P27_11") (pintype "unspecified"))
    )
    (net (code "45") (name "Net-(U5-P32)") (class "Default")
      (node (ref "R26") (pin "1") (pinfunction "1_1") (pintype "unspecified"))
      (node (ref "U5") (pin "7") (pinfunction "P32_7") (pintype "unspecified"))
    )
    (net (code "46") (name "Net-(U5-RX)") (class "Default")
      (node (ref "R47") (pin "1") (pinfunction "1_1") (pintype "unspecified"))
      (node (ref "U5") (pin "34") (pinfunction "RX_34") (pintype "unspecified"))
    )
    (net (code "47") (name "Net-(U5-TX)") (class "Default")
      (node (ref "R46") (pin "1") (pinfunction "1_1") (pintype "unspecified"))
      (node (ref "U5") (pin "35") (pinfunction "TX_35") (pintype "unspecified"))
    )
    (net (code "48") (name "Net-(U8-RC_THROTTLE_SIGNAL)") (class "Default")
      (node (ref "R30") (pin "1") (pinfunction "1_1") (pintype "unspecified"))
      (node (ref "U8") (pin "3") (pinfunction "RC_THROTTLE_SIGNAL_3") (pintype "unspecified"))
    )
    (net (code "49") (name "Net-(U9-PWM_PUMP_Yellow)") (class "Default")
      (node (ref "R20") (pin "1") (pinfunction "1_1") (pintype "unspecified"))
      (node (ref "R22") (pin "2") (pinfunction "2_2") (pintype "unspecified"))
      (node (ref "U9") (pin "3") (pinfunction "PWM_PUMP_Yellow_3") (pintype "unspecified"))
    )
    (net (code "50") (name "Net-(U11-RC_MODE_SIGNAL)") (class "Default")
      (node (ref "R31") (pin "2") (pinfunction "2_2") (pintype "unspecified"))
      (node (ref "U11") (pin "3") (pinfunction "RC_MODE_SIGNAL_3") (pintype "unspecified"))
    )
    (net (code "51") (name "Net-(U18-IN1-)") (class "Default")
      (node (ref "R37") (pin "1") (pinfunction "1_1") (pintype "unspecified"))
      (node (ref "R38") (pin "2") (pinfunction "2_2") (pintype "unspecified"))
      (node (ref "U18") (pin "2") (pinfunction "IN1-_2") (pintype "unspecified"))
    )
    (net (code "52") (name "Net-(U18-IN2-)") (class "Default")
      (node (ref "R34") (pin "2") (pinfunction "2_2") (pintype "unspecified"))
      (node (ref "RP2") (pin "1") (pinfunction "1_1") (pintype "input"))
      (node (ref "RP2") (pin "2") (pinfunction "2_2") (pintype "input"))
      (node (ref "U18") (pin "6") (pinfunction "IN2-_6") (pintype "unspecified"))
    )
    (net (code "53") (name "Net-(U18-OUT1)") (class "Default")
      (node (ref "R34") (pin "1") (pinfunction "1_1") (pintype "unspecified"))
      (node (ref "RP1") (pin "2") (pinfunction "2_2") (pintype "input"))
      (node (ref "RP1") (pin "3") (pinfunction "3_3") (pintype "input"))
      (node (ref "U18") (pin "1") (pinfunction "OUT1_1") (pintype "unspecified"))
    )
    (net (code "54") (name "Net-(U19-1IN+)") (class "Default")
      (node (ref "C2") (pin "2") (pinfunction "2_2") (pintype "unspecified"))
      (node (ref "R32") (pin "2") (pinfunction "2_2") (pintype "unspecified"))
      (node (ref "R36") (pin "1") (pinfunction "1_1") (pintype "unspecified"))
      (node (ref "U19") (pin "3") (pinfunction "1IN+_3") (pintype "unspecified"))
    )
    (net (code "55") (name "Net-(U19-2IN+)") (class "Default")
      (node (ref "R1") (pin "2") (pinfunction "2_2") (pintype "unspecified"))
      (node (ref "U19") (pin "5") (pinfunction "2IN+_5") (pintype "unspecified"))
    )
    (net (code "56") (name "Net-(U19-2IN-)") (class "Default")
      (node (ref "R3") (pin "2") (pinfunction "2_2") (pintype "unspecified"))
      (node (ref "U19") (pin "6") (pinfunction "2IN-_6") (pintype "unspecified"))
    )
    (net (code "57") (name "Net-(U20-+IN)") (class "Default")
      (node (ref "C19") (pin "1") (pinfunction "1_1") (pintype "unspecified"))
      (node (ref "R42") (pin "2") (pinfunction "2_2") (pintype "unspecified"))
      (node (ref "U20") (pin "4") (pinfunction "+IN_4") (pintype "unspecified"))
    )
    (net (code "58") (name "Net-(U20--IN)") (class "Default")
      (node (ref "C19") (pin "2") (pinfunction "2_2") (pintype "unspecified"))
      (node (ref "R41") (pin "1") (pinfunction "1_1") (pintype "unspecified"))
      (node (ref "U20") (pin "1") (pinfunction "-IN_1") (pintype "unspecified"))
    )
    (net (code "59") (name "Net-(VALVE_1_CTRL-CTRL_{slash}_PWM)") (class "Default")
      (node (ref "R24") (pin "2") (pinfunction "2_2") (pintype "unspecified"))
      (node (ref "R27") (pin "2") (pinfunction "2_2") (pintype "unspecified"))
      (node (ref "VALVE_1_CTRL") (pin "2") (pinfunction "CTRL_/_PWM_2") (pintype "unspecified"))
    )
    (net (code "60") (name "Net-(VALVE_2_CTRL-CTRL_{slash}_PWM)") (class "Default")
      (node (ref "R25") (pin "2") (pinfunction "2_2") (pintype "unspecified"))
      (node (ref "R29") (pin "2") (pinfunction "2_2") (pintype "unspecified"))
      (node (ref "VALVE_2_CTRL") (pin "2") (pinfunction "CTRL_/_PWM_2") (pintype "unspecified"))
    )
    (net (code "61") (name "RPM_OUT") (class "Default")
      (node (ref "J_RPM_OUT1") (pin "3") (pinfunction "RPM_OUT_3") (pintype "unspecified"))
      (node (ref "R36") (pin "2") (pinfunction "2_2") (pintype "unspecified"))
      (node (ref "U19") (pin "1") (pinfunction "1OUT_1") (pintype "unspecified"))
      (node (ref "U2") (pin "1") (pinfunction "1_1") (pintype "unspecified"))
    )
    (net (code "62") (name "SENSOR_N") (class "Default")
      (node (ref "R41") (pin "2") (pinfunction "2_2") (pintype "unspecified"))
      (node (ref "U12") (pin "1") (pinfunction "1_1") (pintype "unspecified"))
      (node (ref "U17") (pin "3") (pinfunction "-V0_3") (pintype "unspecified"))
    )
    (net (code "63") (name "SENSOR_P") (class "Default")
      (node (ref "R42") (pin "1") (pinfunction "1_1") (pintype "unspecified"))
      (node (ref "U13") (pin "1") (pinfunction "1_1") (pintype "unspecified"))
      (node (ref "U17") (pin "1") (pinfunction "+V0_1") (pintype "unspecified"))
    )
    (net (code "64") (name "VREF") (class "Default")
      (node (ref "C1") (pin "2") (pinfunction "2_2") (pintype "unspecified"))
      (node (ref "C23") (pin "2") (pinfunction "2_2") (pintype "unspecified"))
      (node (ref "R35") (pin "1") (pinfunction "1_1") (pintype "unspecified"))
      (node (ref "R39") (pin "2") (pinfunction "2_2") (pintype "unspecified"))
      (node (ref "R40") (pin "1") (pinfunction "1_1") (pintype "unspecified"))
      (node (ref "U14") (pin "1") (pinfunction "1_1") (pintype "unspecified"))
      (node (ref "U18") (pin "3") (pinfunction "IN1+_3") (pintype "unspecified"))
      (node (ref "U18") (pin "5") (pinfunction "IN2+_5") (pintype "unspecified"))
      (node (ref "U20") (pin "6") (pinfunction "REF_6") (pintype "unspecified"))
    )
    (net (code "65") (name "VTH_RPM") (class "Default")
      (node (ref "C16") (pin "1") (pinfunction "1_1") (pintype "unspecified"))
      (node (ref "RP3") (pin "2") (pinfunction "2_2") (pintype "input"))
      (node (ref "U19") (pin "2") (pinfunction "1IN-_2") (pintype "unspecified"))
      (node (ref "U21") (pin "1") (pinfunction "1_1") (pintype "unspecified"))
    )
    (net (code "66") (name "unconnected-(GSU_DEBUG_UART1-SHIELD{slash}NC-Pad4)") (class "Default")
      (node (ref "GSU_DEBUG_UART1") (pin "4") (pinfunction "SHIELD/NC_4") (pintype "unspecified"))
    )
    (net (code "67") (name "unconnected-(TMP_PIN_IN1-SHIELD{slash}NC-Pad6)") (class "Default")
      (node (ref "TMP_PIN_IN1") (pin "6") (pinfunction "SHIELD/NC_6") (pintype "unspecified"))
    )
    (net (code "68") (name "unconnected-(TMP_PIN_OUT1-SHIELD{slash}NC-Pad6)") (class "Default")
      (node (ref "TMP_PIN_OUT1") (pin "6") (pinfunction "SHIELD/NC_6") (pintype "unspecified"))
    )
    (net (code "69") (name "unconnected-(U4-BEC_5V_NC_Red-Pad2)") (class "Default")
      (node (ref "U4") (pin "2") (pinfunction "BEC_5V_NC_Red_2") (pintype "unspecified"))
    )
    (net (code "70") (name "unconnected-(U5-CLK-Pad20)") (class "Default")
      (node (ref "U5") (pin "20") (pinfunction "CLK_20") (pintype "unspecified"))
    )
    (net (code "71") (name "unconnected-(U5-CMD-Pad18)") (class "Default")
      (node (ref "U5") (pin "18") (pinfunction "CMD_18") (pintype "unspecified"))
    )
    (net (code "72") (name "unconnected-(U5-EN-Pad2)") (class "Default")
      (node (ref "U5") (pin "2") (pinfunction "EN_2") (pintype "unspecified"))
    )
    (net (code "73") (name "unconnected-(U5-GND-Pad32)") (class "Default")
      (node (ref "U5") (pin "32") (pinfunction "GND_32") (pintype "unspecified"))
    )
    (net (code "74") (name "unconnected-(U5-P0-Pad25)") (class "Default")
      (node (ref "U5") (pin "25") (pinfunction "P0_25") (pintype "unspecified"))
    )
    (net (code "75") (name "unconnected-(U5-P2-Pad24)") (class "Default")
      (node (ref "U5") (pin "24") (pinfunction "P2_24") (pintype "unspecified"))
    )
    (net (code "76") (name "unconnected-(U5-P4-Pad26)") (class "Default")
      (node (ref "U5") (pin "26") (pinfunction "P4_26") (pintype "unspecified"))
    )
    (net (code "77") (name "unconnected-(U5-P12-Pad13)") (class "Default")
      (node (ref "U5") (pin "13") (pinfunction "P12_13") (pintype "unspecified"))
    )
    (net (code "78") (name "unconnected-(U5-P15-Pad23)") (class "Default")
      (node (ref "U5") (pin "23") (pinfunction "P15_23") (pintype "unspecified"))
    )
    (net (code "79") (name "unconnected-(U5-P21-Pad33)") (class "Default")
      (node (ref "U5") (pin "33") (pinfunction "P21_33") (pintype "unspecified"))
    )
    (net (code "80") (name "unconnected-(U5-SD0-Pad21)") (class "Default")
      (node (ref "U5") (pin "21") (pinfunction "SD0_21") (pintype "unspecified"))
    )
    (net (code "81") (name "unconnected-(U5-SD1-Pad22)") (class "Default")
      (node (ref "U5") (pin "22") (pinfunction "SD1_22") (pintype "unspecified"))
    )
    (net (code "82") (name "unconnected-(U5-SD2-Pad16)") (class "Default")
      (node (ref "U5") (pin "16") (pinfunction "SD2_16") (pintype "unspecified"))
    )
    (net (code "83") (name "unconnected-(U5-SD3-Pad17)") (class "Default")
      (node (ref "U5") (pin "17") (pinfunction "SD3_17") (pintype "unspecified"))
    )
    (net (code "84") (name "unconnected-(U5-SVN{slash}P39-Pad4)") (class "Default")
      (node (ref "U5") (pin "4") (pinfunction "SVN/P39_4") (pintype "unspecified"))
    )
    (net (code "85") (name "unconnected-(U5-SVP{slash}P36-Pad3)") (class "Default")
      (node (ref "U5") (pin "3") (pinfunction "SVP/P36_3") (pintype "unspecified"))
    )
    (net (code "86") (name "unconnected-(U8-+5V_RC_{slash}_NC-Pad2)") (class "Default")
      (node (ref "U8") (pin "2") (pinfunction "+5V_RC_/_NC_2") (pintype "unspecified"))
    )
    (net (code "87") (name "unconnected-(U9-BEC_5V_NC_Red-Pad2)") (class "Default")
      (node (ref "U9") (pin "2") (pinfunction "BEC_5V_NC_Red_2") (pintype "unspecified"))
    )
    (net (code "88") (name "unconnected-(U11-+5V_RC_{slash}_NC-Pad2)") (class "Default")
      (node (ref "U11") (pin "2") (pinfunction "+5V_RC_/_NC_2") (pintype "unspecified"))
    )
    (net (code "89") (name "unconnected-(U19-2OUT-Pad7)") (class "Default")
      (node (ref "U19") (pin "7") (pinfunction "2OUT_7") (pintype "unspecified"))
    )
  )
)
